# THYRISTOR_POWER_REGULATOR.net
KiCad netlist of a schematic drawn in Altium Designer
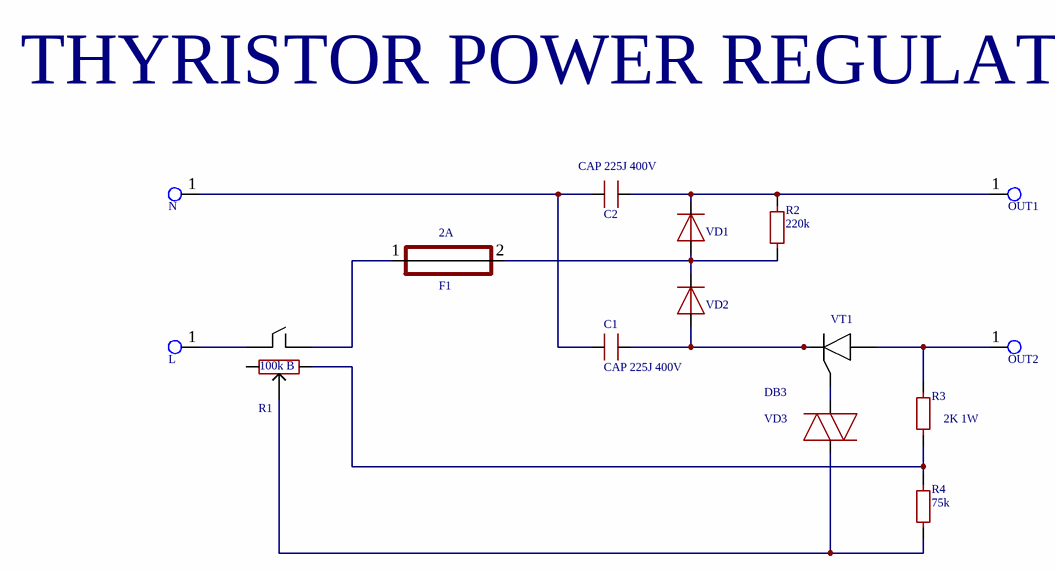
[diagram p0: THYRISTOR POWER REGULATOR.SchDoc]

(export (version "E")
  (design (tool "Eeschema 10.0.6"))
  (components
    (comp (ref "C1")
      (value "CAP 225J 400V")
      (footprint "CAP 225J 400V")
      (libsource (lib "CAP 225J 400V") (part "CAP 225J 400V"))
    )
    (comp (ref "C2")
      (value "CAP 225J 400V")
      (footprint "CAP 225J 400V")
      (libsource (lib "CAP 225J 400V") (part "CAP 225J 400V"))
    )
    (comp (ref "F1") (value "2A") (footprint "BMS 2S") (libsource (lib "fuse") (part "F?")))
    (comp (ref "L")
      (value "Test_Point_PCB")
      (footprint "Test_Point")
      (description "Test_Point")
      (libsource (lib "TEST_POINT") (part "TP_PCB?"))
    )
    (comp (ref "N")
      (value "Test_Point_PCB")
      (footprint "Test_Point")
      (description "Test_Point")
      (libsource (lib "") (part "TP_PCB?_1"))
    )
    (comp (ref "OUT1")
      (value "Test_Point_PCB")
      (footprint "Test_Point")
      (description "Test_Point")
      (libsource (lib "TEST_POINT") (part "TP_PCB?"))
    )
    (comp (ref "OUT2")
      (value "Test_Point_PCB")
      (footprint "Test_Point")
      (description "Test_Point")
      (libsource (lib "TEST_POINT") (part "TP_PCB?"))
    )
    (comp (ref "R1") (value "100k B") (footprint "RES_VAR") (libsource (lib "RES_VAR") (part "RES_VAR")))
    (comp (ref "R2")
      (value "220k")
      (footprint "RES-1206")
      (libsource (lib "PASSIVE_COMPONENTS") (part "RES-CONST"))
    )
    (comp (ref "R3")
      (value "2K 1W")
      (footprint "RES-2512")
      (libsource (lib "PASSIVE_COMPONENTS") (part "RES-CONST"))
    )
    (comp (ref "R4")
      (value "75k")
      (footprint "RES-1206")
      (libsource (lib "PASSIVE_COMPONENTS") (part "RES-CONST"))
    )
    (comp (ref "VD1")
      (value "DIODE")
      (footprint "DO-214AA")
      (description "Diode Schottky 40 V 3A Surface Mount SMB")
      (fields (field (name "PART NUMBER") "B340B-13-F") (field (name "MANUFACTURER") "Diodes Incorporated"))
      (libsource (lib "Database_Libs2") (part "DIODE"))
    )
    (comp (ref "VD2")
      (value "DIODE")
      (footprint "DO-214AA")
      (description "Diode Schottky 40 V 3A Surface Mount SMB")
      (fields (field (name "PART NUMBER") "B340B-13-F") (field (name "MANUFACTURER") "Diodes Incorporated"))
      (libsource (lib "Database_Libs2") (part "DIODE"))
    )
    (comp (ref "VD3") (value "DB3") (footprint "DB3") (libsource (lib "DB3") (part "DIODE")))
    (comp (ref "VT1") (value "TYN412") (footprint "TO-220-3") (libsource (lib "TYN412") (part "TYN412")))
  )
  (nets
    (net (code "1") (name "Net-(C1-A)") (class "Default")
      (node (ref "C1") (pin "2") (pinfunction "A_2") (pintype "passive"))
      (node (ref "C2") (pin "2") (pinfunction "A_2") (pintype "passive"))
      (node (ref "N") (pin "1") (pinfunction "G9_1") (pintype "passive"))
    )
    (net (code "2") (name "Net-(C1-C)") (class "Default")
      (node (ref "C1") (pin "1") (pinfunction "C_1") (pintype "passive"))
      (node (ref "VD2") (pin "2") (pinfunction "A_2") (pintype "passive"))
      (node (ref "VT1") (pin "1") (pintype "passive"))
    )
    (net (code "3") (name "Net-(C2-C)") (class "Default")
      (node (ref "C2") (pin "1") (pinfunction "C_1") (pintype "passive"))
      (node (ref "OUT1") (pin "1") (pinfunction "G9_1") (pintype "passive"))
      (node (ref "R2") (pin "1") (pinfunction "1_1") (pintype "passive"))
      (node (ref "VD1") (pin "1") (pinfunction "C_1") (pintype "passive"))
    )
    (net (code "4") (name "Net-(F1-Pad1)") (class "Default")
      (node (ref "F1") (pin "1") (pintype "passive"))
      (node (ref "R1") (pin "4") (pintype "passive"))
    )
    (net (code "5") (name "Net-(L-G9)") (class "Default")
      (node (ref "L") (pin "1") (pinfunction "G9_1") (pintype "passive"))
      (node (ref "R1") (pin "5") (pintype "passive"))
    )
    (net (code "6") (name "Net-(OUT2-G9)") (class "Default")
      (node (ref "OUT2") (pin "1") (pinfunction "G9_1") (pintype "passive"))
      (node (ref "R3") (pin "2") (pinfunction "2_2") (pintype "passive"))
      (node (ref "VT1") (pin "2") (pintype "passive"))
    )
    (net (code "7") (name "Net-(R1-Pad1)") (class "Default")
      (node (ref "R1") (pin "1") (pintype "passive"))
      (node (ref "R3") (pin "1") (pinfunction "1_1") (pintype "passive"))
      (node (ref "R4") (pin "1") (pinfunction "1_1") (pintype "passive"))
    )
    (net (code "8") (name "Net-(VD1-A)") (class "Default")
      (node (ref "F1") (pin "2") (pintype "passive"))
      (node (ref "R2") (pin "2") (pinfunction "2_2") (pintype "passive"))
      (node (ref "VD1") (pin "2") (pinfunction "A_2") (pintype "passive"))
      (node (ref "VD2") (pin "1") (pinfunction "C_1") (pintype "passive"))
    )
    (net (code "9") (name "Net-(VD3-A)") (class "Default")
      (node (ref "R1") (pin "2") (pintype "passive"))
      (node (ref "R4") (pin "2") (pinfunction "2_2") (pintype "passive"))
      (node (ref "VD3") (pin "2") (pinfunction "A_2") (pintype "passive"))
    )
    (net (code "10") (name "Net-(VD3-C)") (class "Default")
      (node (ref "VD3") (pin "1") (pinfunction "C_1") (pintype "passive"))
      (node (ref "VT1") (pin "3") (pintype "passive"))
    )
    (net (code "11") (name "unconnected-(R1-Pad3)") (class "Default")
      (node (ref "R1") (pin "3") (pintype "passive"))
    )
  )
)
